# RS422_point_to_point.net
KiCad netlist of a schematic drawn in Altium Designer
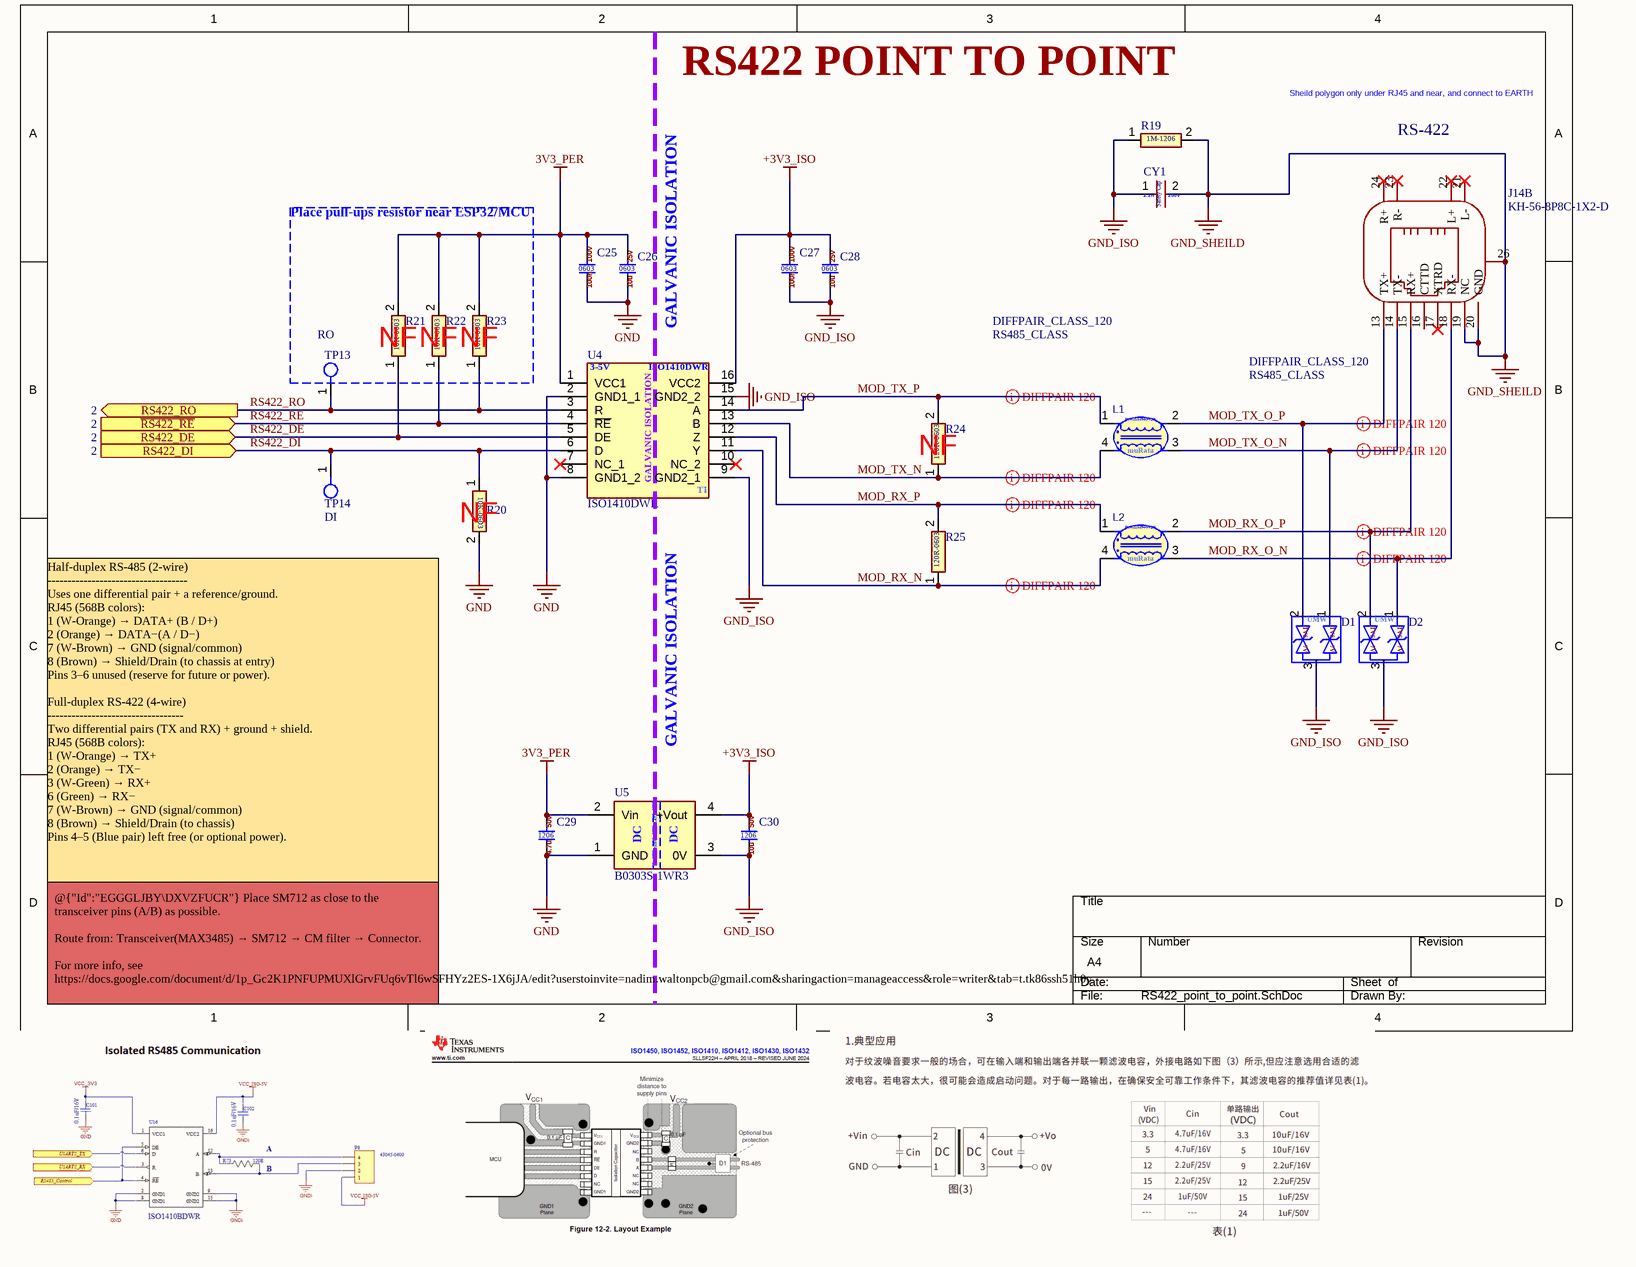
[diagram p0: RS422_point_to_point.SchDoc]

(export (version "E")
  (design (tool "Eeschema 10.0.6"))
  (components
    (comp (ref "C25")
      (value "CL10B104KC8NNNC")
      (footprint "0603-CAP")
      (description "CAP: CER 100NF 100V X7R 0603")
      (fields (field (name "LCSC PART #") "C15725"))
      (libsource (lib "Nadim Altium Lib-Univ") (part "CL10B104KC8NNNC"))
    )
    (comp (ref "C26")
      (value "CL10A106MA8NRNC")
      (footprint "0603-CAP")
      (description "CAP: CER 10UF 25V X5R 0603")
      (fields (field (name "LCSC PART #") "C96446"))
      (libsource (lib "Nadim Altium Lib-Univ") (part "CL10A106MA8NRNC"))
    )
    (comp (ref "C27")
      (value "CL10B104KC8NNNC")
      (footprint "0603-CAP")
      (description "CAP: CER 100NF 100V X7R 0603")
      (fields (field (name "LCSC PART #") "C15725"))
      (libsource (lib "Nadim Altium Lib-Univ") (part "CL10B104KC8NNNC"))
    )
    (comp (ref "C28")
      (value "CL10A106MA8NRNC")
      (footprint "0603-CAP")
      (description "CAP: CER 10UF 25V X5R 0603")
      (fields (field (name "LCSC PART #") "C96446"))
      (libsource (lib "Nadim Altium Lib-Univ") (part "CL10A106MA8NRNC"))
    )
    (comp (ref "C29")
      (value "CL31B475KBHNNNE")
      (footprint "1206-CAP")
      (description "CAP: CER 4.7UF 50V X7R 1206")
      (fields (field (name "LCSC PART #") "C51205"))
      (libsource (lib "Nadim Altium Lib-Univ") (part "CL31B475KBHNNNE"))
    )
    (comp (ref "C30")
      (value "CL31A106KBHNNNE")
      (footprint "1206-CAP")
      (description "CAP: CER 10UF 35V X5R 1206")
      (fields (field (name "LCSC PART #") "C13585"))
      (libsource (lib "Nadim Altium Lib-Univ") (part "CL31A106KBHNNNE"))
    )
    (comp (ref "CY1")
      (value "G08F1E222MN0B0S0N0")
      (footprint "CAP_SAFETY_P7.5MM")
      (description "CAP SAFETY: 2.2nF ±20% 250V TH P7.5mm")
      (fields (field (name "LCSC PART #") "C240878"))
      (libsource (lib "Nadim Altium Lib-Univ") (part "G08F1E222MN0B0S0N0"))
    )
    (comp (ref "D1")
      (value "SM712(UMW)")
      (footprint "SOT-23-3")
      (description "DIODE TVS: 7V WM 11VC Voltage - Breakdown (Min) 6V\r\nSOT-23")
      (fields (field (name "LCSC PART #") "C7436899"))
      (libsource (lib "Nadim Altium Lib-Univ") (part "SM712(UMW)"))
    )
    (comp (ref "D2")
      (value "SM712(UMW)")
      (footprint "SOT-23-3")
      (description "DIODE TVS: 7V WM 11VC Voltage - Breakdown (Min) 6V\r\nSOT-23")
      (fields (field (name "LCSC PART #") "C7436899"))
      (libsource (lib "Nadim Altium Lib-Univ") (part "SM712(UMW)"))
    )
    (comp (ref "J14")
      (value "KH-56-8P8C-1X2-D")
      (footprint "RJ45-TH_KH-56-8P8C-1X2-D")
      (fields (field (name "LCSC PART #") "C2828088"))
      (libsource (lib "Nadim Altium Lib-Univ") (part "KH-56-8P8C-1X2-D_1"))
    )
    (comp (ref "L1")
      (value "DLW21SZ900HQ2L")
      (footprint "FILTER-SMD_4P-L2.0-W1.2-BL_DLW21H")
      (description "Filter CM: 90Ω@100MHz 410mΩ 2 0805 Common Mode Filters ROHS")
      (fields (field (name "LCSC PART #") "C161093"))
      (libsource (lib "Nadim Altium Lib-Univ") (part "DLW21SZ900HQ2L"))
    )
    (comp (ref "L2")
      (value "DLW21SZ900HQ2L")
      (footprint "FILTER-SMD_4P-L2.0-W1.2-BL_DLW21H")
      (description "Filter CM: 90Ω@100MHz 410mΩ 2 0805 Common Mode Filters ROHS")
      (fields (field (name "LCSC PART #") "C161093"))
      (libsource (lib "Nadim Altium Lib-Univ") (part "DLW21SZ900HQ2L"))
    )
    (comp (ref "R19")
      (value "1206W4F1004T5E")
      (footprint "1206-RES")
      (description "RES: 1M OHM 1% 1/4W\r\n1206")
      (fields (field (name "LCSC PART #") "C17927"))
      (libsource (lib "Nadim Altium Lib-Univ") (part "1206W4F1004T5E"))
    )
    (comp (ref "R20")
      (value "0603WAF1002T5E")
      (footprint "0603-RES")
      (description "RES: 10K OHM 1% 100mW 0603 75V")
      (fields (field (name "LCSC PART #") "C25804"))
      (libsource (lib "") (part "0603WAF1002T5E_1"))
    )
    (comp (ref "R21")
      (value "0603WAF1002T5E")
      (footprint "0603-RES")
      (description "RES: 10K OHM 1% 100mW 0603 75V")
      (fields (field (name "LCSC PART #") "C25804"))
      (libsource (lib "Nadim Altium Lib-Univ") (part "0603WAF1002T5E"))
    )
    (comp (ref "R22")
      (value "0603WAF1002T5E")
      (footprint "0603-RES")
      (description "RES: 10K OHM 1% 100mW 0603 75V")
      (fields (field (name "LCSC PART #") "C25804"))
      (libsource (lib "Nadim Altium Lib-Univ") (part "0603WAF1002T5E"))
    )
    (comp (ref "R23")
      (value "0603WAF1002T5E")
      (footprint "0603-RES")
      (description "RES: 10K OHM 1% 100mW 0603 75V")
      (fields (field (name "LCSC PART #") "C25804"))
      (libsource (lib "Nadim Altium Lib-Univ") (part "0603WAF1002T5E"))
    )
    (comp (ref "R24")
      (value "0603WAF1200T5E")
      (footprint "0603-RES")
      (description "RES: 120R OHM 1% 100mW 0603 75V")
      (fields (field (name "LCSC PART #") "C22787"))
      (libsource (lib "Nadim Altium Lib-Univ") (part "0603WAF1200T5E"))
    )
    (comp (ref "R25")
      (value "0603WAF1200T5E")
      (footprint "0603-RES")
      (description "RES: 120R OHM 1% 100mW 0603 75V")
      (fields (field (name "LCSC PART #") "C22787"))
      (libsource (lib "Nadim Altium Lib-Univ") (part "0603WAF1200T5E"))
    )
    (comp (ref "TP13")
      (value "RO")
      (footprint "Test Pad FP")
      (description "TESTPAD: Test Pad")
      (libsource (lib "Nadim Altium Lib-Univ") (part "Test Pad"))
    )
    (comp (ref "TP14")
      (value "DI")
      (footprint "Test Pad FP")
      (description "TESTPAD: Test Pad")
      (libsource (lib "Nadim Altium Lib-Univ") (part "Test Pad"))
    )
    (comp (ref "U4")
      (value "ISO1410DWR")
      (footprint "Nadim Altium Lib-Univ:SOIC-16-300mil")
      (description "MODBUS: Galvanic Isolated 3-5V Full and Half-Duplex RS-485 RS-422 Transceivers")
      (fields (field (name "LCSC PART #") "C2671566"))
      (libsource (lib "Nadim Altium Lib-Univ") (part "ISO1410DWR"))
    )
    (comp (ref "U5")
      (value "B0303S-1WR3")
      (footprint "EVISUN B0303S-1WR3")
      (fields (field (name "LCSC PART #") "C7465185"))
      (libsource (lib "Nadim Altium Lib-Univ") (part "B0303S-1WR3"))
    )
  )
  (nets
    (net (code "1") (name "+3V3_ISO") (class "Default")
      (node (ref "C27") (pin "2") (pinfunction "2_2") (pintype "passive"))
      (node (ref "C28") (pin "2") (pinfunction "2_2") (pintype "passive"))
      (node (ref "C30") (pin "2") (pinfunction "2_2") (pintype "passive"))
      (node (ref "U4") (pin "16") (pinfunction "VCC2_16") (pintype "passive"))
      (node (ref "U5") (pin "4") (pinfunction "+Vout_4") (pintype "passive"))
    )
    (net (code "2") (name "/MOD_RX_N") (class "Default")
      (node (ref "L2") (pin "4") (pinfunction "4_4") (pintype "passive"))
      (node (ref "R25") (pin "1") (pinfunction "1_1") (pintype "passive"))
      (node (ref "U4") (pin "11") (pinfunction "Y_11") (pintype "passive"))
    )
    (net (code "3") (name "/MOD_RX_O_N") (class "Default")
      (node (ref "D2") (pin "1") (pinfunction "1_1") (pintype "passive"))
      (node (ref "J14") (pin "18") (pinfunction "RX-_18") (pintype "passive"))
      (node (ref "L2") (pin "3") (pinfunction "3_3") (pintype "passive"))
    )
    (net (code "4") (name "/MOD_RX_O_P") (class "Default")
      (node (ref "D2") (pin "2") (pinfunction "2_2") (pintype "passive"))
      (node (ref "J14") (pin "15") (pinfunction "RX+_15") (pintype "passive"))
      (node (ref "L2") (pin "2") (pinfunction "2_2") (pintype "passive"))
    )
    (net (code "5") (name "/MOD_RX_P") (class "Default")
      (node (ref "L2") (pin "1") (pinfunction "1_1") (pintype "passive"))
      (node (ref "R25") (pin "2") (pinfunction "2_2") (pintype "passive"))
      (node (ref "U4") (pin "12") (pinfunction "Z_12") (pintype "passive"))
    )
    (net (code "6") (name "/MOD_TX_N") (class "Default")
      (node (ref "L1") (pin "4") (pinfunction "4_4") (pintype "passive"))
      (node (ref "R24") (pin "1") (pinfunction "1_1") (pintype "passive"))
      (node (ref "U4") (pin "13") (pinfunction "B_13") (pintype "passive"))
    )
    (net (code "7") (name "/MOD_TX_O_N") (class "Default")
      (node (ref "D1") (pin "1") (pinfunction "1_1") (pintype "passive"))
      (node (ref "J14") (pin "14") (pinfunction "TX-_14") (pintype "passive"))
      (node (ref "L1") (pin "3") (pinfunction "3_3") (pintype "passive"))
    )
    (net (code "8") (name "/MOD_TX_O_P") (class "Default")
      (node (ref "D1") (pin "2") (pinfunction "2_2") (pintype "passive"))
      (node (ref "J14") (pin "13") (pinfunction "TX+_13") (pintype "passive"))
      (node (ref "L1") (pin "2") (pinfunction "2_2") (pintype "passive"))
    )
    (net (code "9") (name "/MOD_TX_P") (class "Default")
      (node (ref "L1") (pin "1") (pinfunction "1_1") (pintype "passive"))
      (node (ref "R24") (pin "2") (pinfunction "2_2") (pintype "passive"))
      (node (ref "U4") (pin "14") (pinfunction "A_14") (pintype "passive"))
    )
    (net (code "10") (name "/RS422_DE") (class "Default")
      (node (ref "R21") (pin "1") (pinfunction "1_1") (pintype "passive"))
      (node (ref "U4") (pin "5") (pinfunction "DE_5") (pintype "passive"))
    )
    (net (code "11") (name "/RS422_DI") (class "Default")
      (node (ref "R20") (pin "1") (pinfunction "1_1") (pintype "passive"))
      (node (ref "TP14") (pin "1") (pinfunction "1_1") (pintype "passive"))
      (node (ref "U4") (pin "6") (pinfunction "D_6") (pintype "passive"))
    )
    (net (code "12") (name "/RS422_RE") (class "Default")
      (node (ref "R22") (pin "1") (pinfunction "1_1") (pintype "passive"))
      (node (ref "U4") (pin "4") (pinfunction "~{RE}_4") (pintype "passive"))
    )
    (net (code "13") (name "/RS422_RO") (class "Default")
      (node (ref "R23") (pin "1") (pinfunction "1_1") (pintype "passive"))
      (node (ref "TP13") (pin "1") (pinfunction "1_1") (pintype "passive"))
      (node (ref "U4") (pin "3") (pinfunction "R_3") (pintype "passive"))
    )
    (net (code "14") (name "3V3_PER") (class "Default")
      (node (ref "C25") (pin "2") (pinfunction "2_2") (pintype "passive"))
      (node (ref "C26") (pin "2") (pinfunction "2_2") (pintype "passive"))
      (node (ref "C29") (pin "2") (pinfunction "2_2") (pintype "passive"))
      (node (ref "R21") (pin "2") (pinfunction "2_2") (pintype "passive"))
      (node (ref "R22") (pin "2") (pinfunction "2_2") (pintype "passive"))
      (node (ref "R23") (pin "2") (pinfunction "2_2") (pintype "passive"))
      (node (ref "U4") (pin "1") (pinfunction "VCC1_1") (pintype "passive"))
      (node (ref "U5") (pin "2") (pinfunction "Vin_2") (pintype "passive"))
    )
    (net (code "15") (name "GND") (class "Default")
      (node (ref "C25") (pin "1") (pinfunction "1_1") (pintype "passive"))
      (node (ref "C26") (pin "1") (pinfunction "1_1") (pintype "passive"))
      (node (ref "C29") (pin "1") (pinfunction "1_1") (pintype "passive"))
      (node (ref "R20") (pin "2") (pinfunction "2_2") (pintype "passive"))
      (node (ref "U4") (pin "2") (pinfunction "GND1_1_2") (pintype "passive"))
      (node (ref "U4") (pin "8") (pinfunction "GND1_2_8") (pintype "passive"))
      (node (ref "U5") (pin "1") (pinfunction "GND_1") (pintype "passive"))
    )
    (net (code "16") (name "GND_ISO") (class "Default")
      (node (ref "C27") (pin "1") (pinfunction "1_1") (pintype "passive"))
      (node (ref "C28") (pin "1") (pinfunction "1_1") (pintype "passive"))
      (node (ref "C30") (pin "1") (pinfunction "1_1") (pintype "passive"))
      (node (ref "CY1") (pin "1") (pinfunction "1_1") (pintype "passive"))
      (node (ref "D1") (pin "3") (pinfunction "3_3") (pintype "passive"))
      (node (ref "D2") (pin "3") (pinfunction "3_3") (pintype "passive"))
      (node (ref "R19") (pin "1") (pinfunction "1_1") (pintype "passive"))
      (node (ref "U4") (pin "15") (pinfunction "GND2_2_15") (pintype "passive"))
      (node (ref "U4") (pin "9") (pinfunction "GND2_1_9") (pintype "passive"))
      (node (ref "U5") (pin "3") (pinfunction "0V_3") (pintype "passive"))
    )
    (net (code "17") (name "GND_SHEILD") (class "Default")
      (node (ref "CY1") (pin "2") (pinfunction "2_2") (pintype "passive"))
      (node (ref "J14") (pin "19") (pinfunction "NC_19") (pintype "passive"))
      (node (ref "J14") (pin "20") (pinfunction "GND_20") (pintype "passive"))
      (node (ref "J14") (pin "26") (pinfunction "SHELL_26") (pintype "passive"))
      (node (ref "R19") (pin "2") (pinfunction "2_2") (pintype "passive"))
    )
    (net (code "18") (name "unconnected-(J14B-CTTD-Pad16)") (class "Default")
      (node (ref "J14") (pin "16") (pinfunction "CTTD_16") (pintype "passive"))
    )
    (net (code "19") (name "unconnected-(J14B-L+-Pad22)") (class "Default")
      (node (ref "J14") (pin "22") (pinfunction "L+_22") (pintype "passive+no_connect"))
    )
    (net (code "20") (name "unconnected-(J14B-L--Pad21)") (class "Default")
      (node (ref "J14") (pin "21") (pinfunction "L-_21") (pintype "passive+no_connect"))
    )
    (net (code "21") (name "unconnected-(J14B-R+-Pad24)") (class "Default")
      (node (ref "J14") (pin "24") (pinfunction "R+_24") (pintype "passive+no_connect"))
    )
    (net (code "22") (name "unconnected-(J14B-R--Pad23)") (class "Default")
      (node (ref "J14") (pin "23") (pinfunction "R-_23") (pintype "passive+no_connect"))
    )
    (net (code "23") (name "unconnected-(J14B-XTRD-Pad17)") (class "Default")
      (node (ref "J14") (pin "17") (pinfunction "XTRD_17") (pintype "passive+no_connect"))
    )
    (net (code "24") (name "unconnected-(U4-NC_1-Pad7)") (class "Default")
      (node (ref "U4") (pin "7") (pinfunction "NC_1_7") (pintype "passive+no_connect"))
    )
    (net (code "25") (name "unconnected-(U4-NC_2-Pad10)") (class "Default")
      (node (ref "U4") (pin "10") (pinfunction "NC_2_10") (pintype "passive+no_connect"))
    )
  )
)
